# CAN.net
KiCad netlist of a schematic drawn in Altium Designer
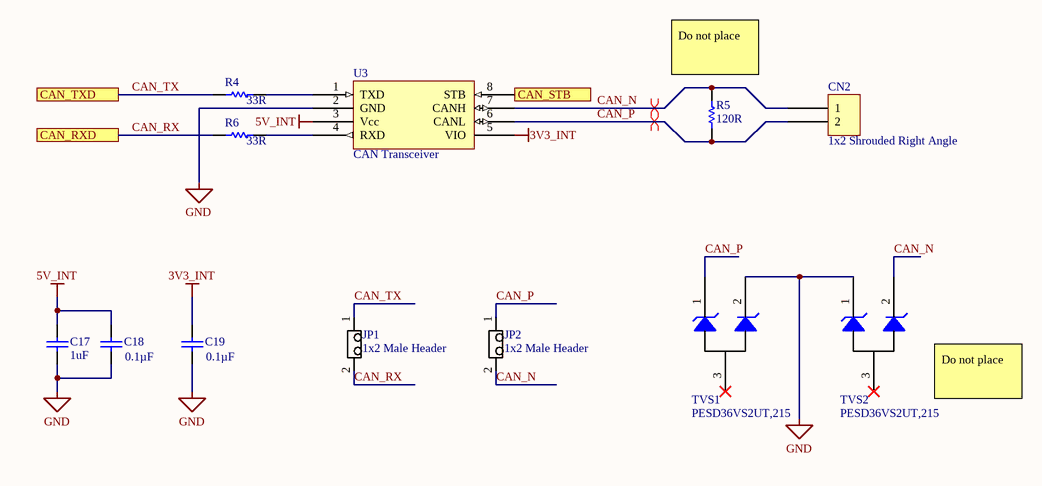
[diagram p0: CAN.SchDoc]

(export (version "E")
  (design (tool "Eeschema 10.0.6"))
  (components
    (comp (ref "C17")
      (value "CL21B105KBFNNNG")
      (footprint "0803 CAP")
      (description "SAMSUNG ELECTRO-MECHANICS - CL21B105KBFNNNG - MLCC CAPACITORS")
      (fields
        (field (name "TOLERANCE") "10%")
        (field (name "CAPACITANCE") "1uF")
        (field (name "VOLTAGE") "50V")
      )
      (libsource (lib "") (part "Symbol_1"))
    )
    (comp (ref "C18")
      (value "0.1µF")
      (footprint "CAPC2012N(0805\")")
      (description "Capacitor, Ceramic, 50V, +/-5%, 0805 SMD, X7R")
      (fields
        (field (name "Comment") "0.1uF 50V 0805 SMD, Ceramic")
        (field (name "SOURCE") "AUVic_Schematic_Library_Capacitors.SchLib")
        (field (name "PUBLISHER") "AUVic")
      )
      (libsource (lib "AUVIC") (part "Symbol"))
    )
    (comp (ref "C19")
      (value "0.1µF")
      (footprint "CAPC2012N(0805\")")
      (description "Capacitor, Ceramic, 50V, +/-5%, 0805 SMD, X7R")
      (fields
        (field (name "Comment") "0.1uF 50V 0805 SMD, Ceramic")
        (field (name "SOURCE") "AUVic_Schematic_Library_Capacitors.SchLib")
        (field (name "PUBLISHER") "AUVic")
      )
      (libsource (lib "AUVIC") (part "Symbol"))
    )
    (comp (ref "CN2")
      (value "1x2 Shrouded Right Angle")
      (footprint "2X1 Female Header")
      (description "02 MTE HDR SRRA LATCH")
      (libsource (lib "AUVIC") (part "1x2 Shrouded Right Angle"))
    )
    (comp (ref "JP1")
      (value "1x2 Male Header")
      (footprint "2X1 Males Header")
      (fields
        (field (name "SOURCE") "AUVic_Schematic_Library_Connectors.SchLib")
        (field (name "MADE BY") "Andy Bates")
      )
      (libsource (lib "AUVIC") (part "1x2 Male Header"))
    )
    (comp (ref "JP2")
      (value "1x2 Male Header")
      (footprint "2X1 Males Header")
      (fields
        (field (name "SOURCE") "AUVic_Schematic_Library_Connectors.SchLib")
        (field (name "MADE BY") "Andy Bates")
      )
      (libsource (lib "AUVIC") (part "1x2 Male Header"))
    )
    (comp (ref "R4")
      (value "33R")
      (footprint "RESC1608X55X25LL10T15")
      (description "Res Thick Film 0603 33 Ohm 1% 1/10W +/-100ppm/ßC Molded SMD Paper T/R")
      (fields (field (name "TOLERANCE") "1%"))
      (libsource (lib "AUVIC") (part "RES-2"))
    )
    (comp (ref "R5")
      (value "120R")
      (footprint "RESC1608X55X25LL10T15")
      (description "Res Thick Film 0603 120 Ohm 1% 0.1W(1/10W) ±100ppm/C Epoxy SMD T/R")
      (fields (field (name "TOLERANCE") "1%"))
      (libsource (lib "AUVIC") (part "RES-2"))
    )
    (comp (ref "R6")
      (value "33R")
      (footprint "RESC1608X55X25LL10T15")
      (description "Res Thick Film 0603 33 Ohm 1% 1/10W +/-100ppm/ßC Molded SMD Paper T/R")
      (fields (field (name "TOLERANCE") "1%"))
      (libsource (lib "AUVIC") (part "RES-2"))
    )
    (comp (ref "TVS1")
      (value "PESD36VS2UT,215")
      (footprint "SOT95P245X110-3N")
      (description "TVS DIODE 36V 60V SOT23")
      (fields
        (field (name "CREATED BY") "Miguel Manguerra")
        (field (name "SOURCE") "AUVic_Schematic_Library_Diodes.SchLib")
      )
      (libsource (lib "AUVIC") (part "PESD36VS2UT,215"))
    )
    (comp (ref "TVS2")
      (value "PESD36VS2UT,215")
      (footprint "SOT95P245X110-3N")
      (description "TVS DIODE 36V 60V SOT23")
      (fields
        (field (name "CREATED BY") "Miguel Manguerra")
        (field (name "SOURCE") "AUVic_Schematic_Library_Diodes.SchLib")
      )
      (libsource (lib "AUVIC") (part "PESD36VS2UT,215"))
    )
    (comp (ref "U3")
      (value "CAN Transceiver")
      (footprint "8-SOIC")
      (description "1/1 Transceiver Half CANbus 8-SO")
      (libsource (lib "AUVIC") (part "CAN Transceiver"))
    )
  )
  (nets
    (net (code "1") (name "/CAN_N") (class "Default")
      (node (ref "CN2") (pin "1") (pinfunction "1_1") (pintype "passive"))
      (node (ref "JP2") (pin "2") (pinfunction "2_2") (pintype "passive"))
      (node (ref "R5") (pin "2") (pinfunction "2_2") (pintype "passive"))
      (node (ref "TVS2") (pin "2") (pinfunction "Cathode_2_2") (pintype "passive"))
      (node (ref "U3") (pin "7") (pinfunction "CANH_7") (pintype "bidirectional"))
    )
    (net (code "2") (name "/CAN_P") (class "Default")
      (node (ref "CN2") (pin "2") (pinfunction "2_2") (pintype "passive"))
      (node (ref "JP2") (pin "1") (pinfunction "1_1") (pintype "passive"))
      (node (ref "R5") (pin "1") (pinfunction "1_1") (pintype "passive"))
      (node (ref "TVS1") (pin "1") (pinfunction "Cathode_1_1") (pintype "passive"))
      (node (ref "U3") (pin "6") (pinfunction "CANL_6") (pintype "bidirectional"))
    )
    (net (code "3") (name "/CAN_RX") (class "Default")
      (node (ref "JP1") (pin "2") (pinfunction "2_2") (pintype "passive"))
      (node (ref "R6") (pin "1") (pinfunction "1_1") (pintype "passive"))
    )
    (net (code "4") (name "/CAN_STB") (class "Default")
      (node (ref "U3") (pin "8") (pinfunction "STB_8") (pintype "input"))
    )
    (net (code "5") (name "/CAN_TX") (class "Default")
      (node (ref "JP1") (pin "1") (pinfunction "1_1") (pintype "passive"))
      (node (ref "R4") (pin "1") (pinfunction "1_1") (pintype "passive"))
    )
    (net (code "6") (name "3V3_INT") (class "Default")
      (node (ref "C19") (pin "2") (pinfunction "Cathode_2") (pintype "passive"))
      (node (ref "U3") (pin "5") (pinfunction "VIO_5") (pintype "passive"))
    )
    (net (code "7") (name "5V_INT") (class "Default")
      (node (ref "C17") (pin "2") (pinfunction "2_2") (pintype "passive"))
      (node (ref "C18") (pin "2") (pinfunction "Cathode_2") (pintype "passive"))
      (node (ref "U3") (pin "3") (pinfunction "Vcc_3") (pintype "power_in"))
    )
    (net (code "8") (name "GND") (class "Default")
      (node (ref "C17") (pin "1") (pinfunction "1_1") (pintype "passive"))
      (node (ref "C18") (pin "1") (pinfunction "Anode_1") (pintype "passive"))
      (node (ref "C19") (pin "1") (pinfunction "Anode_1") (pintype "passive"))
      (node (ref "TVS1") (pin "2") (pinfunction "Cathode_2_2") (pintype "passive"))
      (node (ref "TVS2") (pin "1") (pinfunction "Cathode_1_1") (pintype "passive"))
      (node (ref "U3") (pin "2") (pinfunction "GND_2") (pintype "power_in"))
    )
    (net (code "9") (name "Net-(U3-RXD)") (class "Default")
      (node (ref "R6") (pin "2") (pinfunction "2_2") (pintype "passive"))
      (node (ref "U3") (pin "4") (pinfunction "RXD_4") (pintype "output"))
    )
    (net (code "10") (name "Net-(U3-TXD)") (class "Default")
      (node (ref "R4") (pin "2") (pinfunction "2_2") (pintype "passive"))
      (node (ref "U3") (pin "1") (pinfunction "TXD_1") (pintype "input"))
    )
    (net (code "11") (name "unconnected-(TVS1-Common_Anode-Pad3)") (class "Default")
      (node (ref "TVS1") (pin "3") (pinfunction "Common_Anode_3") (pintype "passive"))
    )
    (net (code "12") (name "unconnected-(TVS2-Common_Anode-Pad3)") (class "Default")
      (node (ref "TVS2") (pin "3") (pinfunction "Common_Anode_3") (pintype "passive"))
    )
  )
)
